# B2B_connectors.net
KiCad netlist of a schematic drawn in Altium Designer
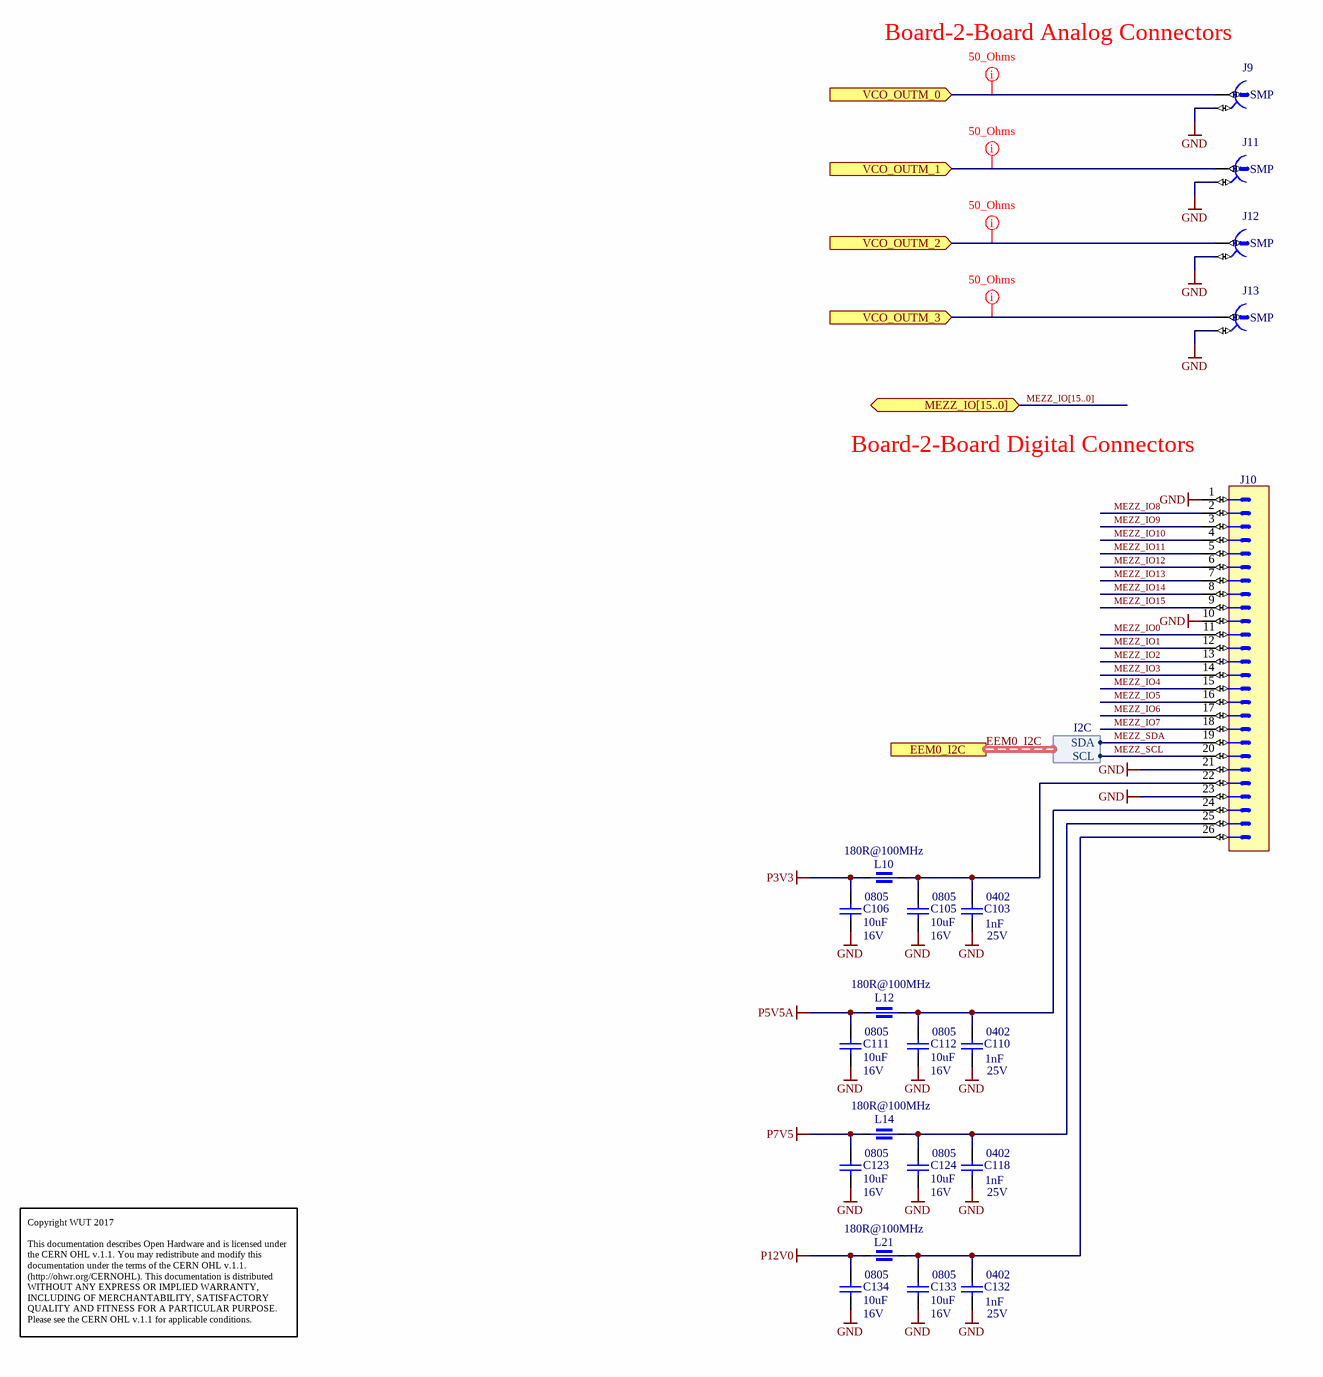
[diagram p0: B2B_connectors.SchDoc]

(export (version "E")
  (design (tool "Eeschema 10.0.6"))
  (components
    (comp (ref "C103")
      (value "1nF")
      (footprint "CAPC1005X55N")
      (description "Non-polarised capacitor")
      (fields
        (field (name "PART NUMBER") "CC0402_1NF_25V_5%_NP0")
        (field (name "VOLTAGE") "25V")
        (field (name "TOLERANCE") "±5%")
        (field (name "CASE") "0402")
        (field (name "AUTHOR") "CERN DEM JLC")
      )
      (libsource (lib "Capacitors") (part "Capacitor - non polarized"))
    )
    (comp (ref "C105")
      (value "10uF")
      (footprint "CAPC2012X135N")
      (description "Non-polarised capacitor")
      (fields
        (field (name "PART NUMBER") "CC0805_10UF_16V_10%_X7R")
        (field (name "VOLTAGE") "16V")
        (field (name "TOLERANCE") "±10%")
        (field (name "CASE") "0805")
        (field (name "AUTHOR") "CERN DEM JLC")
      )
      (libsource (lib "Capacitors") (part "Capacitor - non polarized"))
    )
    (comp (ref "C106")
      (value "10uF")
      (footprint "CAPC2012X135N")
      (description "Non-polarised capacitor")
      (fields
        (field (name "PART NUMBER") "CC0805_10UF_16V_10%_X7R")
        (field (name "VOLTAGE") "16V")
        (field (name "TOLERANCE") "±10%")
        (field (name "CASE") "0805")
        (field (name "AUTHOR") "CERN DEM JLC")
      )
      (libsource (lib "Capacitors") (part "Capacitor - non polarized"))
    )
    (comp (ref "C110")
      (value "1nF")
      (footprint "CAPC1005X55N")
      (description "Non-polarised capacitor")
      (fields
        (field (name "PART NUMBER") "CC0402_1NF_25V_5%_NP0")
        (field (name "VOLTAGE") "25V")
        (field (name "TOLERANCE") "±5%")
        (field (name "CASE") "0402")
        (field (name "AUTHOR") "CERN DEM JLC")
      )
      (libsource (lib "Capacitors") (part "Capacitor - non polarized"))
    )
    (comp (ref "C111")
      (value "10uF")
      (footprint "CAPC2012X135N")
      (description "Non-polarised capacitor")
      (fields
        (field (name "PART NUMBER") "CC0805_10UF_16V_10%_X7R")
        (field (name "VOLTAGE") "16V")
        (field (name "TOLERANCE") "±10%")
        (field (name "CASE") "0805")
        (field (name "AUTHOR") "CERN DEM JLC")
      )
      (libsource (lib "Capacitors") (part "Capacitor - non polarized"))
    )
    (comp (ref "C112")
      (value "10uF")
      (footprint "CAPC2012X135N")
      (description "Non-polarised capacitor")
      (fields
        (field (name "PART NUMBER") "CC0805_10UF_16V_10%_X7R")
        (field (name "VOLTAGE") "16V")
        (field (name "TOLERANCE") "±10%")
        (field (name "CASE") "0805")
        (field (name "AUTHOR") "CERN DEM JLC")
      )
      (libsource (lib "Capacitors") (part "Capacitor - non polarized"))
    )
    (comp (ref "C118")
      (value "1nF")
      (footprint "CAPC1005X55N")
      (description "Non-polarised capacitor")
      (fields
        (field (name "PART NUMBER") "CC0402_1NF_25V_5%_NP0")
        (field (name "VOLTAGE") "25V")
        (field (name "TOLERANCE") "±5%")
        (field (name "CASE") "0402")
        (field (name "AUTHOR") "CERN DEM JLC")
      )
      (libsource (lib "Capacitors") (part "Capacitor - non polarized"))
    )
    (comp (ref "C123")
      (value "10uF")
      (footprint "CAPC2012X135N")
      (description "Non-polarised capacitor")
      (fields
        (field (name "PART NUMBER") "CC0805_10UF_16V_10%_X7R")
        (field (name "VOLTAGE") "16V")
        (field (name "TOLERANCE") "±10%")
        (field (name "CASE") "0805")
        (field (name "AUTHOR") "CERN DEM JLC")
      )
      (libsource (lib "Capacitors") (part "Capacitor - non polarized"))
    )
    (comp (ref "C124")
      (value "10uF")
      (footprint "CAPC2012X135N")
      (description "Non-polarised capacitor")
      (fields
        (field (name "PART NUMBER") "CC0805_10UF_16V_10%_X7R")
        (field (name "VOLTAGE") "16V")
        (field (name "TOLERANCE") "±10%")
        (field (name "CASE") "0805")
        (field (name "AUTHOR") "CERN DEM JLC")
      )
      (libsource (lib "Capacitors") (part "Capacitor - non polarized"))
    )
    (comp (ref "C132")
      (value "1nF")
      (footprint "CAPC1005X55N")
      (description "Non-polarised capacitor")
      (fields
        (field (name "PART NUMBER") "CC0402_1NF_25V_5%_NP0")
        (field (name "VOLTAGE") "25V")
        (field (name "TOLERANCE") "±5%")
        (field (name "CASE") "0402")
        (field (name "AUTHOR") "CERN DEM JLC")
      )
      (libsource (lib "Capacitors") (part "Capacitor - non polarized"))
    )
    (comp (ref "C133")
      (value "10uF")
      (footprint "CAPC2012X135N")
      (description "Non-polarised capacitor")
      (fields
        (field (name "PART NUMBER") "CC0805_10UF_16V_10%_X7R")
        (field (name "VOLTAGE") "16V")
        (field (name "TOLERANCE") "±10%")
        (field (name "CASE") "0805")
        (field (name "AUTHOR") "CERN DEM JLC")
      )
      (libsource (lib "Capacitors") (part "Capacitor - non polarized"))
    )
    (comp (ref "C134")
      (value "10uF")
      (footprint "CAPC2012X135N")
      (description "Non-polarised capacitor")
      (fields
        (field (name "PART NUMBER") "CC0805_10UF_16V_10%_X7R")
        (field (name "VOLTAGE") "16V")
        (field (name "TOLERANCE") "±10%")
        (field (name "CASE") "0805")
        (field (name "AUTHOR") "CERN DEM JLC")
      )
      (libsource (lib "Capacitors") (part "Capacitor - non polarized"))
    )
    (comp (ref "J9")
      (value "SMP")
      (footprint "MOLEX_85305-0232")
      (fields
        (field (name "PART NUMBER") "MOLEX_85305-0232")
        (field (name "MANUFACTURER") "MOLEX")
        (field (name "MANUFACTURER PART NUMBER") "85305-0232")
        (field (name "AUTHOR") "CERN DEM JMW")
      )
      (libsource (lib "Connectors") (part "Coax_1Male_1Shield"))
    )
    (comp (ref "J10")
      (value "Header 26")
      (footprint "3M_N2526-6002RB")
      (description "Connector 26 Male")
      (fields
        (field (name "PART NUMBER") "3M_N2526-6002RB")
        (field (name "MANUFACTURER") "3M")
        (field (name "AUTHOR") "CERN DEM JLC")
      )
      (libsource (lib "Connectors") (part "Connector 26 Male"))
    )
    (comp (ref "J11")
      (value "SMP")
      (footprint "MOLEX_85305-0232")
      (fields
        (field (name "PART NUMBER") "MOLEX_85305-0232")
        (field (name "MANUFACTURER") "MOLEX")
        (field (name "MANUFACTURER PART NUMBER") "85305-0232")
        (field (name "AUTHOR") "CERN DEM JMW")
      )
      (libsource (lib "Connectors") (part "Coax_1Male_1Shield"))
    )
    (comp (ref "J12")
      (value "SMP")
      (footprint "MOLEX_85305-0232")
      (fields
        (field (name "PART NUMBER") "MOLEX_85305-0232")
        (field (name "MANUFACTURER") "MOLEX")
        (field (name "MANUFACTURER PART NUMBER") "85305-0232")
        (field (name "AUTHOR") "CERN DEM JMW")
      )
      (libsource (lib "Connectors") (part "Coax_1Male_1Shield"))
    )
    (comp (ref "J13")
      (value "SMP")
      (footprint "MOLEX_85305-0232")
      (fields
        (field (name "PART NUMBER") "MOLEX_85305-0232")
        (field (name "MANUFACTURER") "MOLEX")
        (field (name "MANUFACTURER PART NUMBER") "85305-0232")
        (field (name "AUTHOR") "CERN DEM JMW")
      )
      (libsource (lib "Connectors") (part "Coax_1Male_1Shield"))
    )
    (comp (ref "L10")
      (value "180R@100MHz")
      (footprint "INDC4516X180N")
      (fields
        (field (name "PART NUMBER") "IND1806_MURATA_BLM41PG181SN1L")
        (field (name "POWER") "3.5A")
        (field (name "MANUFACTURER") "MURATA")
        (field (name "AUTHOR") "CERN DEM JLC")
      )
      (libsource (lib "") (part "Ferrite Bead_1"))
    )
    (comp (ref "L12")
      (value "180R@100MHz")
      (footprint "INDC4516X180N")
      (fields
        (field (name "PART NUMBER") "IND1806_MURATA_BLM41PG181SN1L")
        (field (name "POWER") "3.5A")
        (field (name "MANUFACTURER") "MURATA")
        (field (name "AUTHOR") "CERN DEM JLC")
      )
      (libsource (lib "Inductors & Transformers") (part "Ferrite Bead"))
    )
    (comp (ref "L14")
      (value "180R@100MHz")
      (footprint "INDC4516X180N")
      (fields
        (field (name "PART NUMBER") "IND1806_MURATA_BLM41PG181SN1L")
        (field (name "POWER") "3.5A")
        (field (name "MANUFACTURER") "MURATA")
        (field (name "AUTHOR") "CERN DEM JLC")
      )
      (libsource (lib "Inductors & Transformers") (part "Ferrite Bead"))
    )
    (comp (ref "L21")
      (value "180R@100MHz")
      (footprint "INDC4516X180N")
      (fields
        (field (name "PART NUMBER") "IND1806_MURATA_BLM41PG181SN1L")
        (field (name "POWER") "3.5A")
        (field (name "MANUFACTURER") "MURATA")
        (field (name "AUTHOR") "CERN DEM JLC")
      )
      (libsource (lib "") (part "Ferrite Bead_1"))
    )
  )
  (nets
    (net (code "3") (name "/MEZZ_IO0") (class "Default")
      (node (ref "J10") (pin "11") (pinfunction "11_11") (pintype "bidirectional"))
    )
    (net (code "4") (name "/MEZZ_IO1") (class "Default")
      (node (ref "J10") (pin "12") (pinfunction "12_12") (pintype "bidirectional"))
    )
    (net (code "5") (name "/MEZZ_IO2") (class "Default")
      (node (ref "J10") (pin "13") (pinfunction "13_13") (pintype "bidirectional"))
    )
    (net (code "6") (name "/MEZZ_IO3") (class "Default")
      (node (ref "J10") (pin "14") (pinfunction "14_14") (pintype "bidirectional"))
    )
    (net (code "7") (name "/MEZZ_IO4") (class "Default")
      (node (ref "J10") (pin "15") (pinfunction "15_15") (pintype "bidirectional"))
    )
    (net (code "8") (name "/MEZZ_IO5") (class "Default")
      (node (ref "J10") (pin "16") (pinfunction "16_16") (pintype "bidirectional"))
    )
    (net (code "9") (name "/MEZZ_IO6") (class "Default")
      (node (ref "J10") (pin "17") (pinfunction "17_17") (pintype "bidirectional"))
    )
    (net (code "10") (name "/MEZZ_IO7") (class "Default")
      (node (ref "J10") (pin "18") (pinfunction "18_18") (pintype "bidirectional"))
    )
    (net (code "11") (name "/MEZZ_IO8") (class "Default")
      (node (ref "J10") (pin "2") (pinfunction "2_2") (pintype "bidirectional"))
    )
    (net (code "12") (name "/MEZZ_IO9") (class "Default")
      (node (ref "J10") (pin "3") (pinfunction "3_3") (pintype "bidirectional"))
    )
    (net (code "13") (name "/MEZZ_IO10") (class "Default")
      (node (ref "J10") (pin "4") (pinfunction "4_4") (pintype "bidirectional"))
    )
    (net (code "14") (name "/MEZZ_IO11") (class "Default")
      (node (ref "J10") (pin "5") (pinfunction "5_5") (pintype "bidirectional"))
    )
    (net (code "15") (name "/MEZZ_IO12") (class "Default")
      (node (ref "J10") (pin "6") (pinfunction "6_6") (pintype "bidirectional"))
    )
    (net (code "16") (name "/MEZZ_IO13") (class "Default")
      (node (ref "J10") (pin "7") (pinfunction "7_7") (pintype "bidirectional"))
    )
    (net (code "17") (name "/MEZZ_IO14") (class "Default")
      (node (ref "J10") (pin "8") (pinfunction "8_8") (pintype "bidirectional"))
    )
    (net (code "18") (name "/MEZZ_IO15") (class "Default")
      (node (ref "J10") (pin "9") (pinfunction "9_9") (pintype "bidirectional"))
    )
    (net (code "20") (name "/MEZZ_SCL") (class "Default")
      (node (ref "J10") (pin "20") (pinfunction "20_20") (pintype "bidirectional"))
    )
    (net (code "21") (name "/MEZZ_SDA") (class "Default")
      (node (ref "J10") (pin "19") (pinfunction "19_19") (pintype "bidirectional"))
    )
    (net (code "22") (name "/VCO_OUTM_0") (class "Default")
      (node (ref "J9") (pin "1") (pinfunction "1_1") (pintype "bidirectional"))
    )
    (net (code "23") (name "/VCO_OUTM_1") (class "Default")
      (node (ref "J11") (pin "1") (pinfunction "1_1") (pintype "bidirectional"))
    )
    (net (code "24") (name "/VCO_OUTM_2") (class "Default")
      (node (ref "J12") (pin "1") (pinfunction "1_1") (pintype "bidirectional"))
    )
    (net (code "25") (name "/VCO_OUTM_3") (class "Default")
      (node (ref "J13") (pin "1") (pinfunction "1_1") (pintype "bidirectional"))
    )
    (net (code "26") (name "GND") (class "Default")
      (node (ref "C103") (pin "1") (pinfunction "1_1") (pintype "passive"))
      (node (ref "C105") (pin "1") (pinfunction "1_1") (pintype "passive"))
      (node (ref "C106") (pin "1") (pinfunction "1_1") (pintype "passive"))
      (node (ref "C110") (pin "1") (pinfunction "1_1") (pintype "passive"))
      (node (ref "C111") (pin "1") (pinfunction "1_1") (pintype "passive"))
      (node (ref "C112") (pin "1") (pinfunction "1_1") (pintype "passive"))
      (node (ref "C118") (pin "1") (pinfunction "1_1") (pintype "passive"))
      (node (ref "C123") (pin "1") (pinfunction "1_1") (pintype "passive"))
      (node (ref "C124") (pin "1") (pinfunction "1_1") (pintype "passive"))
      (node (ref "C132") (pin "1") (pinfunction "1_1") (pintype "passive"))
      (node (ref "C133") (pin "1") (pinfunction "1_1") (pintype "passive"))
      (node (ref "C134") (pin "1") (pinfunction "1_1") (pintype "passive"))
      (node (ref "J10") (pin "1") (pinfunction "1_1") (pintype "bidirectional"))
      (node (ref "J10") (pin "10") (pinfunction "10_10") (pintype "bidirectional"))
      (node (ref "J10") (pin "21") (pinfunction "21_21") (pintype "bidirectional"))
      (node (ref "J10") (pin "23") (pinfunction "23_23") (pintype "bidirectional"))
      (node (ref "J11") (pin "2") (pinfunction "2_2") (pintype "bidirectional"))
      (node (ref "J12") (pin "2") (pinfunction "2_2") (pintype "bidirectional"))
      (node (ref "J13") (pin "2") (pinfunction "2_2") (pintype "bidirectional"))
      (node (ref "J9") (pin "2") (pinfunction "2_2") (pintype "bidirectional"))
    )
    (net (code "27") (name "Net-(C103-Pad2)") (class "Default")
      (node (ref "C103") (pin "2") (pinfunction "2_2") (pintype "passive"))
      (node (ref "C105") (pin "2") (pinfunction "2_2") (pintype "passive"))
      (node (ref "J10") (pin "22") (pinfunction "22_22") (pintype "bidirectional"))
      (node (ref "L10") (pin "1") (pinfunction "1_1") (pintype "passive"))
    )
    (net (code "28") (name "Net-(C110-Pad2)") (class "Default")
      (node (ref "C110") (pin "2") (pinfunction "2_2") (pintype "passive"))
      (node (ref "C112") (pin "2") (pinfunction "2_2") (pintype "passive"))
      (node (ref "J10") (pin "24") (pinfunction "24_24") (pintype "bidirectional"))
      (node (ref "L12") (pin "2") (pinfunction "2_2") (pintype "passive"))
    )
    (net (code "29") (name "Net-(C118-Pad2)") (class "Default")
      (node (ref "C118") (pin "2") (pinfunction "2_2") (pintype "passive"))
      (node (ref "C124") (pin "2") (pinfunction "2_2") (pintype "passive"))
      (node (ref "J10") (pin "25") (pinfunction "25_25") (pintype "bidirectional"))
      (node (ref "L14") (pin "2") (pinfunction "2_2") (pintype "passive"))
    )
    (net (code "30") (name "Net-(C132-Pad2)") (class "Default")
      (node (ref "C132") (pin "2") (pinfunction "2_2") (pintype "passive"))
      (node (ref "C133") (pin "2") (pinfunction "2_2") (pintype "passive"))
      (node (ref "J10") (pin "26") (pinfunction "26_26") (pintype "bidirectional"))
      (node (ref "L21") (pin "1") (pinfunction "1_1") (pintype "passive"))
    )
    (net (code "31") (name "P3V3") (class "Default")
      (node (ref "C106") (pin "2") (pinfunction "2_2") (pintype "passive"))
      (node (ref "L10") (pin "2") (pinfunction "2_2") (pintype "passive"))
    )
    (net (code "32") (name "P5V5A") (class "Default")
      (node (ref "C111") (pin "2") (pinfunction "2_2") (pintype "passive"))
      (node (ref "L12") (pin "1") (pinfunction "1_1") (pintype "passive"))
    )
    (net (code "33") (name "P7V5") (class "Default")
      (node (ref "C123") (pin "2") (pinfunction "2_2") (pintype "passive"))
      (node (ref "L14") (pin "1") (pinfunction "1_1") (pintype "passive"))
    )
    (net (code "34") (name "P12V0") (class "Default")
      (node (ref "C134") (pin "2") (pinfunction "2_2") (pintype "passive"))
      (node (ref "L21") (pin "2") (pinfunction "2_2") (pintype "passive"))
    )
  )
)
